# 04_Mechanical.net
KiCad netlist of a schematic drawn in Altium Designer
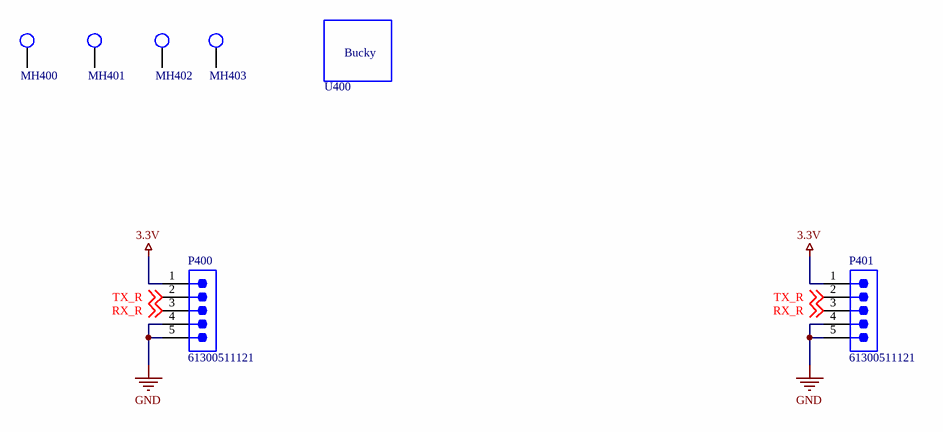
[diagram p0: 04_Mechanical.SchDoc]

(export (version "E")
  (design (tool "Eeschema 10.0.6"))
  (components
    (comp (ref "MH400")
      (value "MHOLE_2_55MM")
      (footprint "MHOLE_2_55MM")
      (description "Mounting Holde")
      (fields (field (name "MANUFACTURER PART NUMBER") "UW MTHOLE"))
      (libsource (lib "ECE453_S24") (part "MHOLE_2_55MM"))
    )
    (comp (ref "MH401")
      (value "MHOLE_2_55MM")
      (footprint "MHOLE_2_55MM")
      (description "Mounting Holde")
      (fields (field (name "MANUFACTURER PART NUMBER") "UW MTHOLE"))
      (libsource (lib "ECE453_S24") (part "MHOLE_2_55MM"))
    )
    (comp (ref "MH402")
      (value "MHOLE_2_55MM")
      (footprint "MHOLE_2_55MM")
      (description "Mounting Holde")
      (fields (field (name "MANUFACTURER PART NUMBER") "UW MTHOLE"))
      (libsource (lib "ECE453_S24") (part "MHOLE_2_55MM"))
    )
    (comp (ref "MH403")
      (value "MHOLE_2_55MM")
      (footprint "MHOLE_2_55MM")
      (description "Mounting Holde")
      (fields (field (name "MANUFACTURER PART NUMBER") "UW MTHOLE"))
      (libsource (lib "ECE453_S24") (part "MHOLE_2_55MM"))
    )
    (comp (ref "P400")
      (value "61300511121")
      (footprint "61300511121")
      (libsource (lib "Altium Content Vault") (part "Header_Male_1R_05P"))
    )
    (comp (ref "P401")
      (value "61300511121")
      (footprint "61300511121")
      (libsource (lib "Altium Content Vault") (part "Header_Male_1R_05P"))
    )
    (comp (ref "U400")
      (value "Bucky")
      (footprint "WalkingBucky")
      (description "Bucky Badger Image")
      (fields (field (name "MANUFACTURER PART NUMBER") "UW Bucky"))
      (libsource (lib "ECE453") (part "Bucky"))
    )
  )
  (nets
    (net (code "1") (name "3.3V") (class "Default")
      (node (ref "P400") (pin "1") (pinfunction "1_1") (pintype "passive"))
      (node (ref "P401") (pin "1") (pinfunction "1_1") (pintype "passive"))
    )
    (net (code "2") (name "GND") (class "Default")
      (node (ref "P400") (pin "4") (pinfunction "4_4") (pintype "passive"))
      (node (ref "P400") (pin "5") (pinfunction "5_5") (pintype "passive"))
      (node (ref "P401") (pin "4") (pinfunction "4_4") (pintype "passive"))
      (node (ref "P401") (pin "5") (pinfunction "5_5") (pintype "passive"))
    )
    (net (code "3") (name "RX_R") (class "Default")
      (node (ref "P400") (pin "3") (pinfunction "3_3") (pintype "passive"))
      (node (ref "P401") (pin "3") (pinfunction "3_3") (pintype "passive"))
    )
    (net (code "4") (name "TX_R") (class "Default")
      (node (ref "P400") (pin "2") (pinfunction "2_2") (pintype "passive"))
      (node (ref "P401") (pin "2") (pinfunction "2_2") (pintype "passive"))
    )
    (net (code "5") (name "unconnected-(MH400-Pad1)") (class "Default")
      (node (ref "MH400") (pin "1") (pintype "passive"))
    )
    (net (code "6") (name "unconnected-(MH401-Pad1)") (class "Default")
      (node (ref "MH401") (pin "1") (pintype "passive"))
    )
    (net (code "7") (name "unconnected-(MH402-Pad1)") (class "Default")
      (node (ref "MH402") (pin "1") (pintype "passive"))
    )
    (net (code "8") (name "unconnected-(MH403-Pad1)") (class "Default")
      (node (ref "MH403") (pin "1") (pintype "passive"))
    )
  )
)
